# W076XX.net
KiCad netlist of a schematic drawn in EAGLE
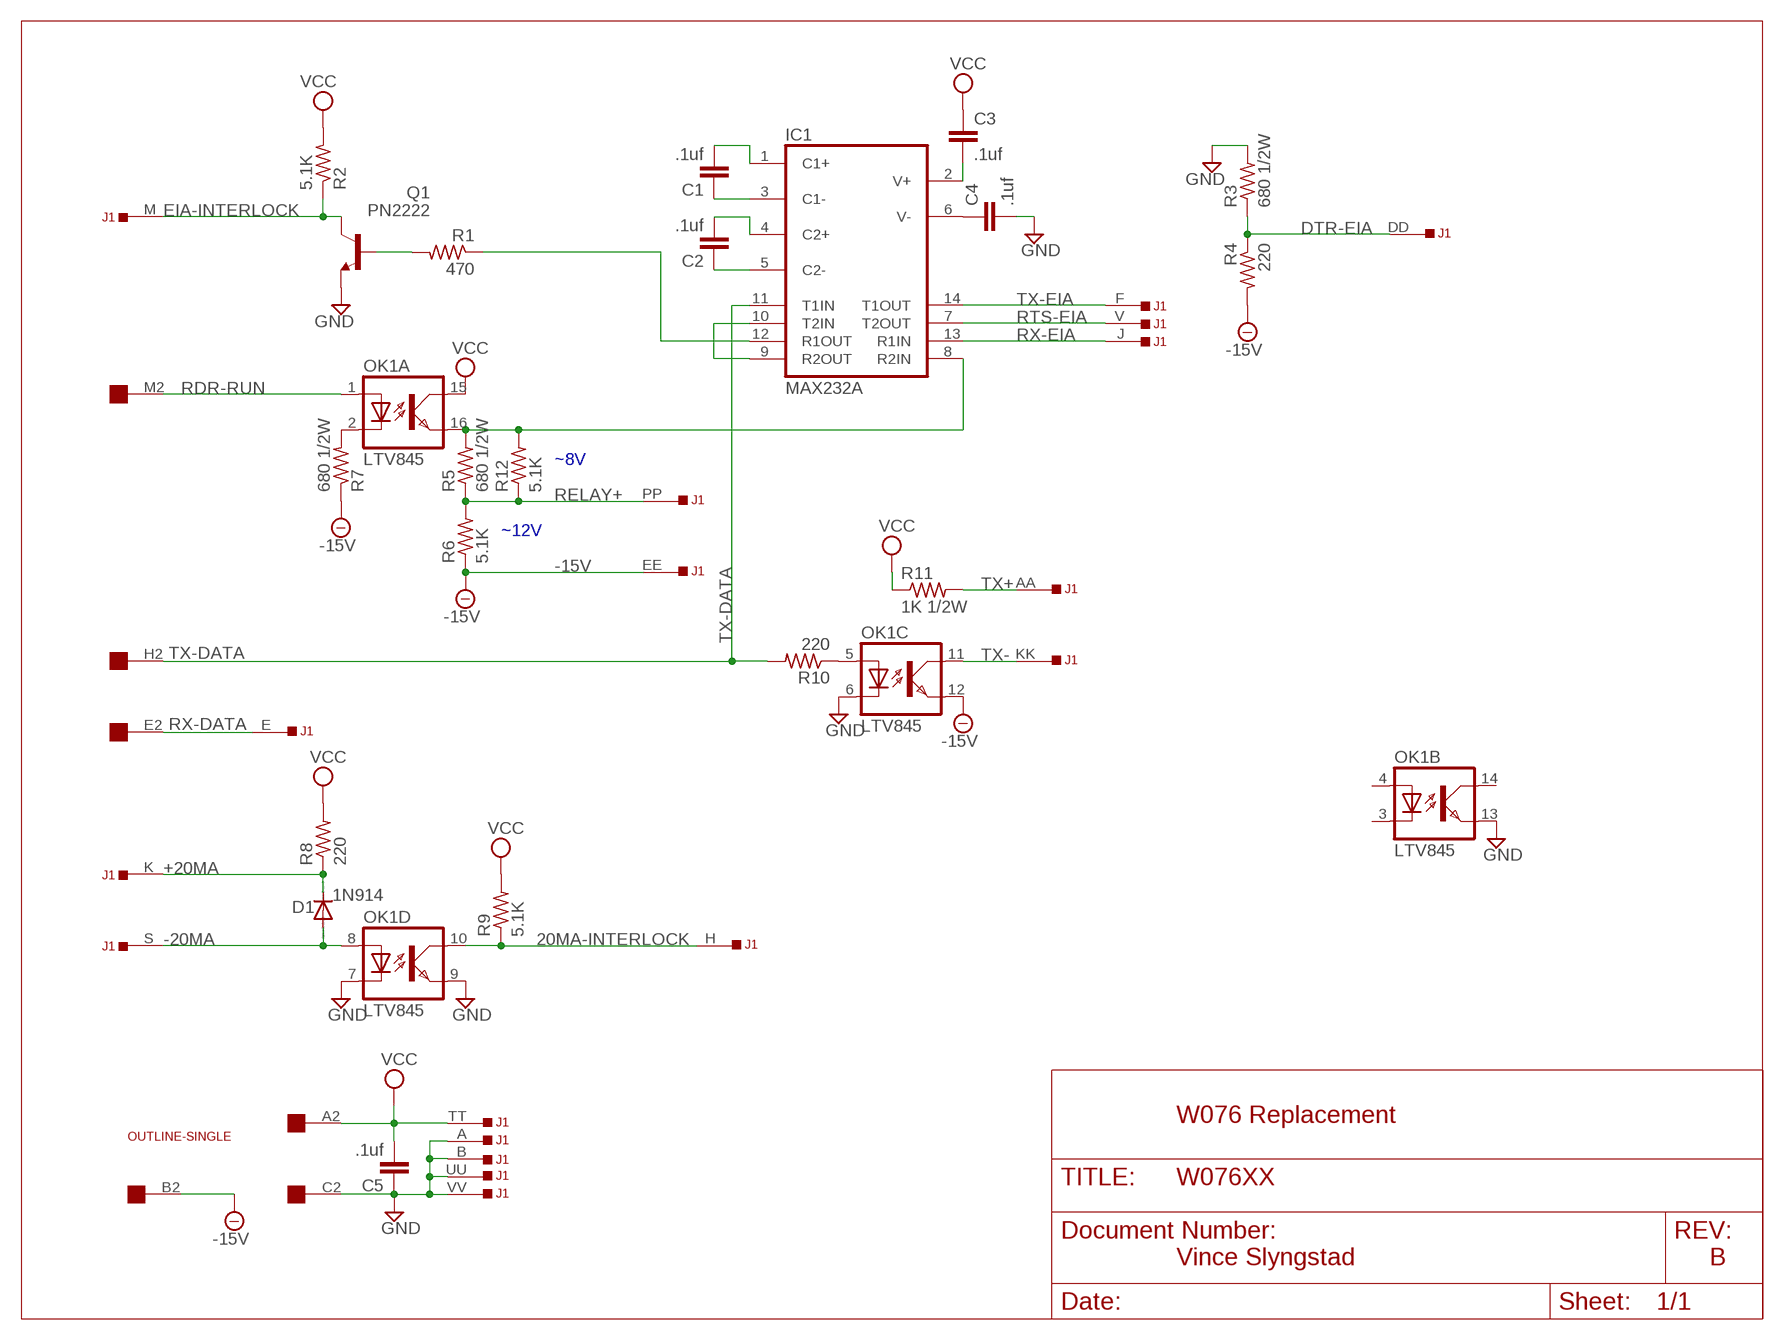
[diagram p0: schematic, sheet 1]

(export (version "E")
  (design (tool "Eeschema 10.0.6"))
  (components
    (comp (ref "C1")
      (value ".1uf")
      (footprint "eagle-import:C050-025X075")
      (libsource (lib "eagle-import") (part "C-EU050-025X075"))
    )
    (comp (ref "C2")
      (value ".1uf")
      (footprint "eagle-import:C050-025X075")
      (libsource (lib "eagle-import") (part "C-EU050-025X075"))
    )
    (comp (ref "C3")
      (value ".1uf")
      (footprint "eagle-import:C050-025X075")
      (libsource (lib "eagle-import") (part "C-EU050-025X075"))
    )
    (comp (ref "C4")
      (value ".1uf")
      (footprint "eagle-import:C050-025X075")
      (libsource (lib "eagle-import") (part "C-EU050-025X075"))
    )
    (comp (ref "C5")
      (value ".1uf")
      (footprint "eagle-import:C050-025X075")
      (libsource (lib "eagle-import") (part "C-EU050-025X075"))
    )
    (comp (ref "D1")
      (value "1N914")
      (footprint "eagle-import:DO41-10")
      (libsource (lib "eagle-import") (part "1N4004"))
    )
    (comp (ref "IC1")
      (value "MAX232A")
      (footprint "eagle-import:DIL16")
      (fields (field (name "MF") "MAXIM") (field (name "MPN") "MAX232ACPE+"))
      (libsource (lib "eagle-import") (part "MAX232"))
    )
    (comp (ref "J1")
      (value "DEC40PINSH")
      (footprint "eagle-import:DEC40PINH")
      (libsource (lib "eagle-import") (part "DEC40PINSH"))
    )
    (comp (ref "OK1")
      (value "LTV845")
      (footprint "eagle-import:DIL16")
      (fields (field (name "MF") "VISHAY/TELEFUNKEN") (field (name "MPN") "ILQ1"))
      (libsource (lib "eagle-import") (part "ILQ1"))
    )
    (comp (ref "Q1")
      (value "PN2222")
      (footprint "eagle-import:TO5")
      (libsource (lib "eagle-import") (part "-NPN-TO5"))
    )
    (comp (ref "R1")
      (value "470")
      (footprint "eagle-import:0207_10")
      (libsource (lib "eagle-import") (part "R-US_0207/10"))
    )
    (comp (ref "R2")
      (value "5.1K")
      (footprint "eagle-import:0207_10")
      (libsource (lib "eagle-import") (part "R-US_0207/10"))
    )
    (comp (ref "R3")
      (value "680 1/2W")
      (footprint "eagle-import:0207_12")
      (libsource (lib "eagle-import") (part "R-US_0207/12"))
    )
    (comp (ref "R4")
      (value "220")
      (footprint "eagle-import:0207_10")
      (libsource (lib "eagle-import") (part "R-US_0207/10"))
    )
    (comp (ref "R5")
      (value "680 1/2W")
      (footprint "eagle-import:0207_12")
      (libsource (lib "eagle-import") (part "R-US_0207/12"))
    )
    (comp (ref "R6")
      (value "5.1K")
      (footprint "eagle-import:0207_10")
      (libsource (lib "eagle-import") (part "R-US_0207/10"))
    )
    (comp (ref "R7")
      (value "680 1/2W")
      (footprint "eagle-import:0207_12")
      (libsource (lib "eagle-import") (part "R-US_0207/12"))
    )
    (comp (ref "R8")
      (value "220")
      (footprint "eagle-import:0207_10")
      (libsource (lib "eagle-import") (part "R-US_0207/10"))
    )
    (comp (ref "R9")
      (value "5.1K")
      (footprint "eagle-import:0207_10")
      (libsource (lib "eagle-import") (part "R-US_0207/10"))
    )
    (comp (ref "R10")
      (value "220")
      (footprint "eagle-import:0207_10")
      (libsource (lib "eagle-import") (part "R-US_0207/10"))
    )
    (comp (ref "R11")
      (value "1K 1/2W")
      (footprint "eagle-import:0207_12")
      (libsource (lib "eagle-import") (part "R-US_0207/12"))
    )
    (comp (ref "R12")
      (value "5.1K")
      (footprint "eagle-import:0207_10")
      (libsource (lib "eagle-import") (part "R-US_0207/10"))
    )
    (comp (ref "U$2")
      (value "EDGE-1")
      (footprint "eagle-import:EDGE-CON1")
      (libsource (lib "eagle-import") (part "EDGE-1"))
    )
    (comp (ref "U$3")
      (value "OUTLINE-SINGLE")
      (footprint "eagle-import:SINGLE")
      (libsource (lib "eagle-import") (part "OUTLINE-SINGLE"))
    )
  )
  (nets
    (net (code "1") (name "-15V") (class "Default")
      (node (ref "J1") (pin "EE") (pinfunction "P_EE") (pintype "passive"))
      (node (ref "OK1") (pin "12") (pinfunction "EMIT_12") (pintype "passive"))
      (node (ref "R4") (pin "2") (pinfunction "2_2") (pintype "passive"))
      (node (ref "R6") (pin "1") (pinfunction "1_1") (pintype "passive"))
      (node (ref "R7") (pin "1") (pinfunction "1_1") (pintype "passive"))
      (node (ref "U$2") (pin "B2") (pinfunction "1_B2") (pintype "bidirectional"))
    )
    (net (code "2") (name "/+20MA") (class "Default")
      (node (ref "D1") (pin "C") (pinfunction "C_C") (pintype "passive"))
      (node (ref "J1") (pin "K") (pinfunction "P_K") (pintype "passive"))
      (node (ref "R8") (pin "1") (pinfunction "1_1") (pintype "passive"))
    )
    (net (code "3") (name "/-20MA") (class "Default")
      (node (ref "D1") (pin "A") (pinfunction "A_A") (pintype "passive"))
      (node (ref "J1") (pin "S") (pinfunction "P_S") (pintype "passive"))
      (node (ref "OK1") (pin "8") (pinfunction "A_8") (pintype "passive"))
    )
    (net (code "4") (name "/20MA-INTERLOCK") (class "Default")
      (node (ref "J1") (pin "H") (pinfunction "P_H") (pintype "passive"))
      (node (ref "OK1") (pin "10") (pinfunction "COL_10") (pintype "passive"))
      (node (ref "R9") (pin "1") (pinfunction "1_1") (pintype "passive"))
    )
    (net (code "5") (name "/DTR-EIA") (class "Default")
      (node (ref "J1") (pin "DD") (pinfunction "P_DD") (pintype "passive"))
      (node (ref "R3") (pin "1") (pinfunction "1_1") (pintype "passive"))
      (node (ref "R4") (pin "1") (pinfunction "1_1") (pintype "passive"))
    )
    (net (code "6") (name "/EIA-INTERLOCK") (class "Default")
      (node (ref "J1") (pin "M") (pinfunction "P_M") (pintype "passive"))
      (node (ref "Q1") (pin "3") (pinfunction "C_3") (pintype "passive"))
      (node (ref "R2") (pin "1") (pinfunction "1_1") (pintype "passive"))
    )
    (net (code "7") (name "/RDR-RUN") (class "Default")
      (node (ref "OK1") (pin "1") (pinfunction "A_1") (pintype "passive"))
      (node (ref "U$2") (pin "M2") (pinfunction "1_M2") (pintype "bidirectional"))
    )
    (net (code "8") (name "/RELAY+") (class "Default")
      (node (ref "J1") (pin "PP") (pinfunction "P_PP") (pintype "passive"))
      (node (ref "R12") (pin "1") (pinfunction "1_1") (pintype "passive"))
      (node (ref "R5") (pin "1") (pinfunction "1_1") (pintype "passive"))
      (node (ref "R6") (pin "2") (pinfunction "2_2") (pintype "passive"))
    )
    (net (code "9") (name "/RTS-EIA") (class "Default")
      (node (ref "IC1") (pin "7") (pinfunction "T2OUT_7") (pintype "output"))
      (node (ref "J1") (pin "V") (pinfunction "P_V") (pintype "passive"))
    )
    (net (code "10") (name "/RX-DATA") (class "Default")
      (node (ref "J1") (pin "E") (pinfunction "P_E") (pintype "passive"))
      (node (ref "U$2") (pin "E2") (pinfunction "1_E2") (pintype "bidirectional"))
    )
    (net (code "11") (name "/RX-EIA") (class "Default")
      (node (ref "IC1") (pin "13") (pinfunction "R1IN_13") (pintype "input"))
      (node (ref "J1") (pin "J") (pinfunction "P_J") (pintype "passive"))
    )
    (net (code "12") (name "/TX+") (class "Default")
      (node (ref "J1") (pin "AA") (pinfunction "P_AA") (pintype "passive"))
      (node (ref "R11") (pin "2") (pinfunction "2_2") (pintype "passive"))
    )
    (net (code "13") (name "/TX-") (class "Default")
      (node (ref "J1") (pin "KK") (pinfunction "P_KK") (pintype "passive"))
      (node (ref "OK1") (pin "11") (pinfunction "COL_11") (pintype "passive"))
    )
    (net (code "14") (name "/TX-DATA") (class "Default")
      (node (ref "IC1") (pin "11") (pinfunction "T1IN_11") (pintype "input"))
      (node (ref "R10") (pin "2") (pinfunction "2_2") (pintype "passive"))
      (node (ref "U$2") (pin "H2") (pinfunction "1_H2") (pintype "bidirectional"))
    )
    (net (code "15") (name "/TX-EIA") (class "Default")
      (node (ref "IC1") (pin "14") (pinfunction "T1OUT_14") (pintype "output"))
      (node (ref "J1") (pin "F") (pinfunction "P_F") (pintype "passive"))
    )
    (net (code "16") (name "GND") (class "Default")
      (node (ref "C4") (pin "2") (pinfunction "2_2") (pintype "passive"))
      (node (ref "C5") (pin "1") (pinfunction "1_1") (pintype "passive"))
      (node (ref "J1") (pin "A") (pinfunction "P_A") (pintype "passive"))
      (node (ref "J1") (pin "B") (pinfunction "P_B") (pintype "passive"))
      (node (ref "J1") (pin "UU") (pinfunction "P_UU") (pintype "passive"))
      (node (ref "J1") (pin "VV") (pinfunction "P_VV") (pintype "passive"))
      (node (ref "OK1") (pin "13") (pinfunction "EMIT_13") (pintype "passive"))
      (node (ref "OK1") (pin "6") (pinfunction "C_6") (pintype "passive"))
      (node (ref "OK1") (pin "7") (pinfunction "C_7") (pintype "passive"))
      (node (ref "OK1") (pin "9") (pinfunction "EMIT_9") (pintype "passive"))
      (node (ref "Q1") (pin "1") (pinfunction "E_1") (pintype "passive"))
      (node (ref "R3") (pin "2") (pinfunction "2_2") (pintype "passive"))
      (node (ref "U$2") (pin "C2") (pinfunction "1_C2") (pintype "bidirectional"))
    )
    (net (code "17") (name "Net-(IC1A-C1+)") (class "Default")
      (node (ref "C1") (pin "2") (pinfunction "2_2") (pintype "passive"))
      (node (ref "IC1") (pin "1") (pinfunction "C1+_1") (pintype "bidirectional"))
    )
    (net (code "18") (name "Net-(IC1A-C1-)") (class "Default")
      (node (ref "C1") (pin "1") (pinfunction "1_1") (pintype "passive"))
      (node (ref "IC1") (pin "3") (pinfunction "C1-_3") (pintype "bidirectional"))
    )
    (net (code "19") (name "Net-(IC1A-C2+)") (class "Default")
      (node (ref "C2") (pin "2") (pinfunction "2_2") (pintype "passive"))
      (node (ref "IC1") (pin "4") (pinfunction "C2+_4") (pintype "bidirectional"))
    )
    (net (code "20") (name "Net-(IC1A-C2-)") (class "Default")
      (node (ref "C2") (pin "1") (pinfunction "1_1") (pintype "passive"))
      (node (ref "IC1") (pin "5") (pinfunction "C2-_5") (pintype "bidirectional"))
    )
    (net (code "21") (name "Net-(IC1A-R1OUT)") (class "Default")
      (node (ref "IC1") (pin "12") (pinfunction "R1OUT_12") (pintype "output"))
      (node (ref "R1") (pin "1") (pinfunction "1_1") (pintype "passive"))
    )
    (net (code "22") (name "Net-(IC1A-R2IN)") (class "Default")
      (node (ref "IC1") (pin "8") (pinfunction "R2IN_8") (pintype "input"))
      (node (ref "OK1") (pin "16") (pinfunction "EMIT_16") (pintype "passive"))
      (node (ref "R12") (pin "2") (pinfunction "2_2") (pintype "passive"))
      (node (ref "R5") (pin "2") (pinfunction "2_2") (pintype "passive"))
    )
    (net (code "23") (name "Net-(IC1A-R2OUT)") (class "Default")
      (node (ref "IC1") (pin "10") (pinfunction "T2IN_10") (pintype "input"))
      (node (ref "IC1") (pin "9") (pinfunction "R2OUT_9") (pintype "output"))
    )
    (net (code "24") (name "Net-(IC1A-V+)") (class "Default")
      (node (ref "C3") (pin "2") (pinfunction "2_2") (pintype "passive"))
      (node (ref "IC1") (pin "2") (pinfunction "V+_2") (pintype "bidirectional"))
    )
    (net (code "25") (name "Net-(IC1A-V-)") (class "Default")
      (node (ref "C4") (pin "1") (pinfunction "1_1") (pintype "passive"))
      (node (ref "IC1") (pin "6") (pinfunction "V-_6") (pintype "bidirectional"))
    )
    (net (code "26") (name "Net-(OK1A-C)") (class "Default")
      (node (ref "OK1") (pin "2") (pinfunction "C_2") (pintype "passive"))
      (node (ref "R7") (pin "2") (pinfunction "2_2") (pintype "passive"))
    )
    (net (code "27") (name "Net-(OK1C-A)") (class "Default")
      (node (ref "OK1") (pin "5") (pinfunction "A_5") (pintype "passive"))
      (node (ref "R10") (pin "1") (pinfunction "1_1") (pintype "passive"))
    )
    (net (code "28") (name "Net-(Q1-B)") (class "Default")
      (node (ref "Q1") (pin "2") (pinfunction "B_2") (pintype "passive"))
      (node (ref "R1") (pin "2") (pinfunction "2_2") (pintype "passive"))
    )
    (net (code "29") (name "VCC") (class "Default")
      (node (ref "C3") (pin "1") (pinfunction "1_1") (pintype "passive"))
      (node (ref "C5") (pin "2") (pinfunction "2_2") (pintype "passive"))
      (node (ref "J1") (pin "TT") (pinfunction "P_TT") (pintype "passive"))
      (node (ref "OK1") (pin "15") (pinfunction "COL_15") (pintype "passive"))
      (node (ref "R11") (pin "1") (pinfunction "1_1") (pintype "passive"))
      (node (ref "R2") (pin "2") (pinfunction "2_2") (pintype "passive"))
      (node (ref "R8") (pin "2") (pinfunction "2_2") (pintype "passive"))
      (node (ref "R9") (pin "2") (pinfunction "2_2") (pintype "passive"))
      (node (ref "U$2") (pin "A2") (pinfunction "1_A2") (pintype "bidirectional"))
    )
    (net (code "30") (name "unconnected-(OK1B-A-Pad4)") (class "Default")
      (node (ref "OK1") (pin "4") (pinfunction "A_4") (pintype "passive"))
    )
    (net (code "31") (name "unconnected-(OK1B-C-Pad3)") (class "Default")
      (node (ref "OK1") (pin "3") (pinfunction "C_3") (pintype "passive"))
    )
    (net (code "32") (name "unconnected-(OK1B-COL-Pad14)") (class "Default")
      (node (ref "OK1") (pin "14") (pinfunction "COL_14") (pintype "passive"))
    )
  )
)
